# Adafruit_3_5in_480x320_FeatherWing_Rev_B.net
KiCad netlist of a schematic drawn in EAGLE
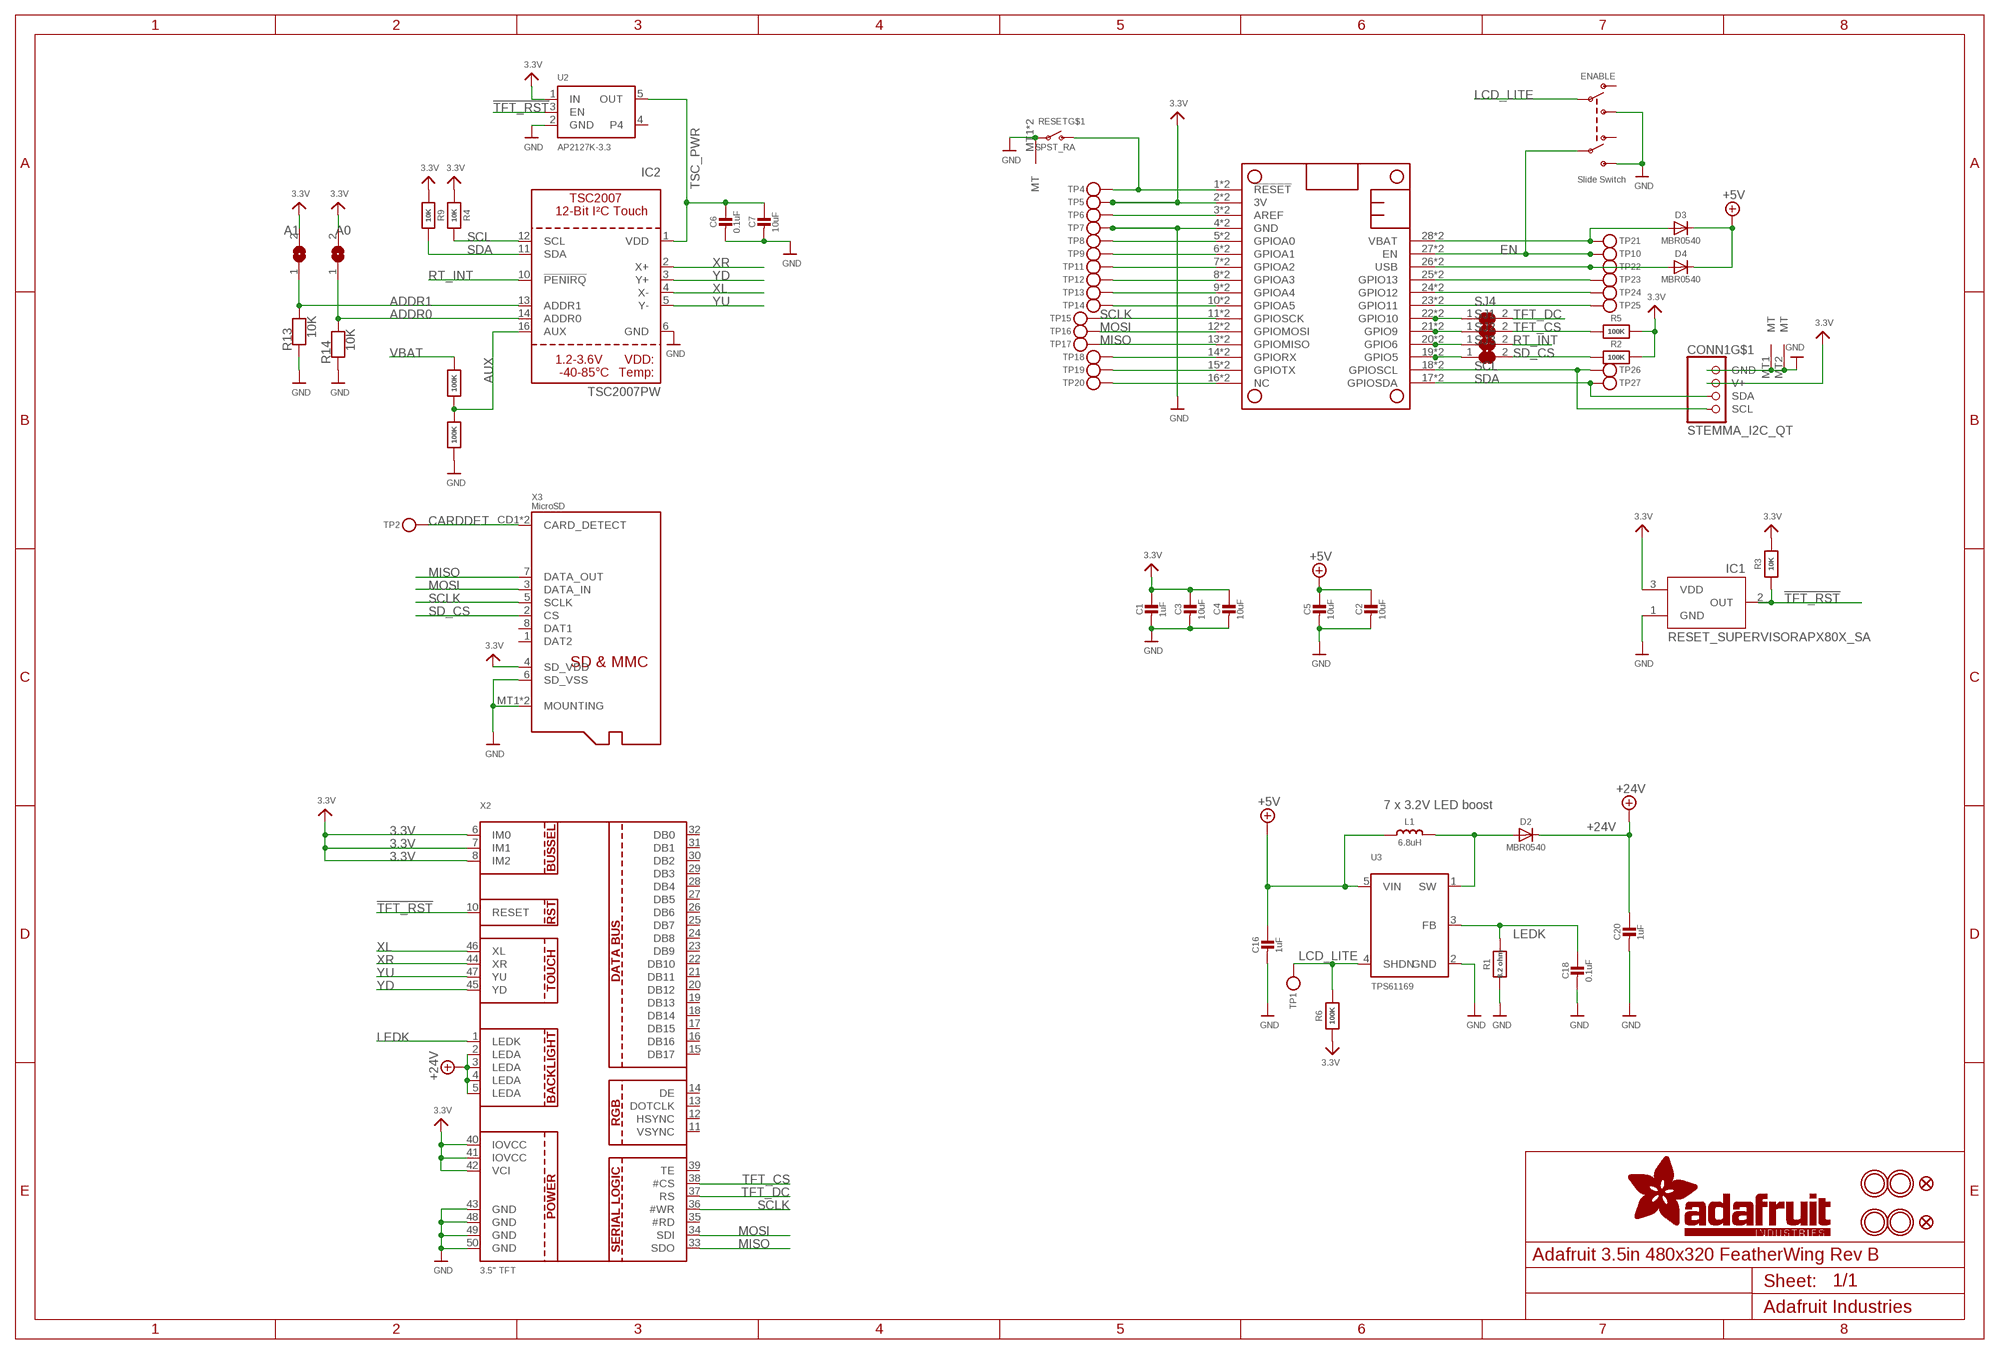
[diagram p0: schematic, sheet 1]

(export (version "E")
  (design (tool "Eeschema 10.0.6"))
  (components
    (comp (ref "C1")
      (value "1uF")
      (footprint "eagle-import:0805-NO")
      (libsource (lib "eagle-import") (part "CAP_CERAMIC0805-NOOUTLINE"))
    )
    (comp (ref "C2")
      (value "10uF")
      (footprint "eagle-import:0805-NO")
      (libsource (lib "eagle-import") (part "CAP_CERAMIC0805-NOOUTLINE"))
    )
    (comp (ref "C3")
      (value "10uF")
      (footprint "eagle-import:0805-NO")
      (libsource (lib "eagle-import") (part "CAP_CERAMIC0805-NOOUTLINE"))
    )
    (comp (ref "C4")
      (value "10uF")
      (footprint "eagle-import:0805-NO")
      (libsource (lib "eagle-import") (part "CAP_CERAMIC0805-NOOUTLINE"))
    )
    (comp (ref "C5")
      (value "10uF")
      (footprint "eagle-import:0805-NO")
      (libsource (lib "eagle-import") (part "CAP_CERAMIC0805-NOOUTLINE"))
    )
    (comp (ref "C6")
      (value "0.1uF")
      (footprint "eagle-import:0603-NO")
      (libsource (lib "eagle-import") (part "CAP_CERAMIC0603_NO"))
    )
    (comp (ref "C7")
      (value "10uF")
      (footprint "eagle-import:0805-NO")
      (libsource (lib "eagle-import") (part "CAP_CERAMIC0805-NOOUTLINE"))
    )
    (comp (ref "C16")
      (value "1uF")
      (footprint "eagle-import:0805-NO")
      (libsource (lib "eagle-import") (part "CAP_CERAMIC0805-NOOUTLINE"))
    )
    (comp (ref "C18")
      (value "0.1uF")
      (footprint "eagle-import:0603-NO")
      (libsource (lib "eagle-import") (part "CAP_CERAMIC0603_NO"))
    )
    (comp (ref "C20")
      (value "1uF")
      (footprint "eagle-import:0805-NO")
      (libsource (lib "eagle-import") (part "CAP_CERAMIC0805-NOOUTLINE"))
    )
    (comp (ref "CONN1")
      (value "STEMMA_I2C_QT")
      (footprint "eagle-import:JST_SH4")
      (libsource (lib "eagle-import") (part "STEMMA_I2C_QT"))
    )
    (comp (ref "D2")
      (value "MBR0540")
      (footprint "eagle-import:SOD-123")
      (libsource (lib "eagle-import") (part "DIODESOD-123"))
    )
    (comp (ref "D3")
      (value "MBR0540")
      (footprint "eagle-import:SOD-123")
      (libsource (lib "eagle-import") (part "DIODESOD-123"))
    )
    (comp (ref "D4")
      (value "MBR0540")
      (footprint "eagle-import:SOD-123")
      (libsource (lib "eagle-import") (part "DIODESOD-123"))
    )
    (comp (ref "ENABLE")
      (value "Slide Switch")
      (footprint "eagle-import:EG1390")
      (libsource (lib "eagle-import") (part "SWITCH_DPDTEG1390"))
    )
    (comp (ref "IC1")
      (value "RESET_SUPERVISORAPX80X_SA")
      (footprint "eagle-import:SOT23-WIDE")
      (libsource (lib "eagle-import") (part "RESET_SUPERVISORAPX80X_SA"))
    )
    (comp (ref "IC2")
      (value "TSC2007PW")
      (footprint "eagle-import:TSSOP16")
      (libsource (lib "eagle-import") (part "TSC2007PW"))
    )
    (comp (ref "ICSP_CLK1")
      (value "A1")
      (footprint "eagle-import:SOLDERJUMPER_ARROW_NOPASTE")
      (libsource (lib "eagle-import") (part "SOLDERJUMPER"))
    )
    (comp (ref "ICSP_CLK2")
      (value "A0")
      (footprint "eagle-import:SOLDERJUMPER_ARROW_NOPASTE")
      (libsource (lib "eagle-import") (part "SOLDERJUMPER"))
    )
    (comp (ref "L1")
      (value "6.8uH")
      (footprint "eagle-import:INDUCTOR_5X5MM_NR5040_NOTHERMALS")
      (libsource (lib "eagle-import") (part "INDUCTORNR5040"))
    )
    (comp (ref "MS2")
      (value "FEATHERWING_SMTDUAL")
      (footprint "eagle-import:FEATHERWING_SMT2")
      (libsource (lib "eagle-import") (part "FEATHERWING_SMTDUAL"))
    )
    (comp (ref "R1")
      (value "8.2 ohm")
      (footprint "eagle-import:0603-NO")
      (libsource (lib "eagle-import") (part "RESISTOR_0603_NOOUT"))
    )
    (comp (ref "R2")
      (value "100K")
      (footprint "eagle-import:0603-NO")
      (libsource (lib "eagle-import") (part "RESISTOR_0603_NOOUT"))
    )
    (comp (ref "R3")
      (value "10K")
      (footprint "eagle-import:0603-NO")
      (libsource (lib "eagle-import") (part "RESISTOR_0603_NOOUT"))
    )
    (comp (ref "R4")
      (value "10K")
      (footprint "eagle-import:0603-NO")
      (libsource (lib "eagle-import") (part "RESISTOR_0603_NOOUT"))
    )
    (comp (ref "R5")
      (value "100K")
      (footprint "eagle-import:0603-NO")
      (libsource (lib "eagle-import") (part "RESISTOR_0603_NOOUT"))
    )
    (comp (ref "R6")
      (value "100K")
      (footprint "eagle-import:0603-NO")
      (libsource (lib "eagle-import") (part "RESISTOR_0603_NOOUT"))
    )
    (comp (ref "R9")
      (value "10K")
      (footprint "eagle-import:0603-NO")
      (libsource (lib "eagle-import") (part "RESISTOR_0603_NOOUT"))
    )
    (comp (ref "R10")
      (value "100K")
      (footprint "eagle-import:0603-NO")
      (libsource (lib "eagle-import") (part "RESISTOR_0603_NOOUT"))
    )
    (comp (ref "R11")
      (value "100K")
      (footprint "eagle-import:0603-NO")
      (libsource (lib "eagle-import") (part "RESISTOR_0603_NOOUT"))
    )
    (comp (ref "R13")
      (value "10K")
      (footprint "eagle-import:0603-NO")
      (libsource (lib "eagle-import") (part "RESISTOR_0603_NOOUT"))
    )
    (comp (ref "R14")
      (value "10K")
      (footprint "eagle-import:0603-NO")
      (libsource (lib "eagle-import") (part "RESISTOR_0603_NOOUT"))
    )
    (comp (ref "RESET")
      (value "SPST_RA")
      (footprint "eagle-import:SPST_TACTILE_RA")
      (libsource (lib "eagle-import") (part "SWITCH_SPST_MNT_TACT_RA"))
    )
    (comp (ref "SJ1")
      (value "SOLDERJUMPER_CLOSED")
      (footprint "eagle-import:SOLDERJUMPER_CLOSEDWIRE")
      (libsource (lib "eagle-import") (part "SOLDERJUMPER_CLOSED"))
    )
    (comp (ref "SJ2")
      (value "SOLDERJUMPER_CLOSED")
      (footprint "eagle-import:SOLDERJUMPER_CLOSEDWIRE")
      (libsource (lib "eagle-import") (part "SOLDERJUMPER_CLOSED"))
    )
    (comp (ref "SJ3")
      (value "SOLDERJUMPER_CLOSED")
      (footprint "eagle-import:SOLDERJUMPER_CLOSEDWIRE")
      (libsource (lib "eagle-import") (part "SOLDERJUMPER_CLOSED"))
    )
    (comp (ref "SJ4")
      (value "SOLDERJUMPER_CLOSED")
      (footprint "eagle-import:SOLDERJUMPER_CLOSEDWIRE")
      (libsource (lib "eagle-import") (part "SOLDERJUMPER_CLOSED"))
    )
    (comp (ref "TP1")
      (value "TESTPOINTPAD2MM")
      (footprint "eagle-import:TESTPOINT_PAD_2MM")
      (libsource (lib "eagle-import") (part "TESTPOINTPAD2MM"))
    )
    (comp (ref "TP2")
      (value "TESTPOINTPAD2MM")
      (footprint "eagle-import:TESTPOINT_PAD_2MM")
      (libsource (lib "eagle-import") (part "TESTPOINTPAD2MM"))
    )
    (comp (ref "TP4")
      (value "TESTPOINTPAD2MM")
      (footprint "eagle-import:TESTPOINT_PAD_2MM")
      (libsource (lib "eagle-import") (part "TESTPOINTPAD2MM"))
    )
    (comp (ref "TP5")
      (value "TESTPOINTPAD2MM")
      (footprint "eagle-import:TESTPOINT_PAD_2MM")
      (libsource (lib "eagle-import") (part "TESTPOINTPAD2MM"))
    )
    (comp (ref "TP6")
      (value "TESTPOINTPAD2MM")
      (footprint "eagle-import:TESTPOINT_PAD_2MM")
      (libsource (lib "eagle-import") (part "TESTPOINTPAD2MM"))
    )
    (comp (ref "TP7")
      (value "TESTPOINTPAD2MM")
      (footprint "eagle-import:TESTPOINT_PAD_2MM")
      (libsource (lib "eagle-import") (part "TESTPOINTPAD2MM"))
    )
    (comp (ref "TP8")
      (value "TESTPOINTPAD2MM")
      (footprint "eagle-import:TESTPOINT_PAD_2MM")
      (libsource (lib "eagle-import") (part "TESTPOINTPAD2MM"))
    )
    (comp (ref "TP9")
      (value "TESTPOINTPAD2MM")
      (footprint "eagle-import:TESTPOINT_PAD_2MM")
      (libsource (lib "eagle-import") (part "TESTPOINTPAD2MM"))
    )
    (comp (ref "TP10")
      (value "TESTPOINTPAD2MM")
      (footprint "eagle-import:TESTPOINT_PAD_2MM")
      (libsource (lib "eagle-import") (part "TESTPOINTPAD2MM"))
    )
    (comp (ref "TP11")
      (value "TESTPOINTPAD2MM")
      (footprint "eagle-import:TESTPOINT_PAD_2MM")
      (libsource (lib "eagle-import") (part "TESTPOINTPAD2MM"))
    )
    (comp (ref "TP12")
      (value "TESTPOINTPAD2MM")
      (footprint "eagle-import:TESTPOINT_PAD_2MM")
      (libsource (lib "eagle-import") (part "TESTPOINTPAD2MM"))
    )
    (comp (ref "TP13")
      (value "TESTPOINTPAD2MM")
      (footprint "eagle-import:TESTPOINT_PAD_2MM")
      (libsource (lib "eagle-import") (part "TESTPOINTPAD2MM"))
    )
    (comp (ref "TP14")
      (value "TESTPOINTPAD2MM")
      (footprint "eagle-import:TESTPOINT_PAD_2MM")
      (libsource (lib "eagle-import") (part "TESTPOINTPAD2MM"))
    )
    (comp (ref "TP15")
      (value "TESTPOINTPAD2MM")
      (footprint "eagle-import:TESTPOINT_PAD_2MM")
      (libsource (lib "eagle-import") (part "TESTPOINTPAD2MM"))
    )
    (comp (ref "TP16")
      (value "TESTPOINTPAD2MM")
      (footprint "eagle-import:TESTPOINT_PAD_2MM")
      (libsource (lib "eagle-import") (part "TESTPOINTPAD2MM"))
    )
    (comp (ref "TP17")
      (value "TESTPOINTPAD2MM")
      (footprint "eagle-import:TESTPOINT_PAD_2MM")
      (libsource (lib "eagle-import") (part "TESTPOINTPAD2MM"))
    )
    (comp (ref "TP18")
      (value "TESTPOINTPAD2MM")
      (footprint "eagle-import:TESTPOINT_PAD_2MM")
      (libsource (lib "eagle-import") (part "TESTPOINTPAD2MM"))
    )
    (comp (ref "TP19")
      (value "TESTPOINTPAD2MM")
      (footprint "eagle-import:TESTPOINT_PAD_2MM")
      (libsource (lib "eagle-import") (part "TESTPOINTPAD2MM"))
    )
    (comp (ref "TP20")
      (value "TESTPOINTPAD2MM")
      (footprint "eagle-import:TESTPOINT_PAD_2MM")
      (libsource (lib "eagle-import") (part "TESTPOINTPAD2MM"))
    )
    (comp (ref "TP21")
      (value "TESTPOINTPAD2MM")
      (footprint "eagle-import:TESTPOINT_PAD_2MM")
      (libsource (lib "eagle-import") (part "TESTPOINTPAD2MM"))
    )
    (comp (ref "TP22")
      (value "TESTPOINTPAD2MM")
      (footprint "eagle-import:TESTPOINT_PAD_2MM")
      (libsource (lib "eagle-import") (part "TESTPOINTPAD2MM"))
    )
    (comp (ref "TP23")
      (value "TESTPOINTPAD2MM")
      (footprint "eagle-import:TESTPOINT_PAD_2MM")
      (libsource (lib "eagle-import") (part "TESTPOINTPAD2MM"))
    )
    (comp (ref "TP24")
      (value "TESTPOINTPAD2MM")
      (footprint "eagle-import:TESTPOINT_PAD_2MM")
      (libsource (lib "eagle-import") (part "TESTPOINTPAD2MM"))
    )
    (comp (ref "TP25")
      (value "TESTPOINTPAD2MM")
      (footprint "eagle-import:TESTPOINT_PAD_2MM")
      (libsource (lib "eagle-import") (part "TESTPOINTPAD2MM"))
    )
    (comp (ref "TP26")
      (value "TESTPOINTPAD2MM")
      (footprint "eagle-import:TESTPOINT_PAD_2MM")
      (libsource (lib "eagle-import") (part "TESTPOINTPAD2MM"))
    )
    (comp (ref "TP27")
      (value "TESTPOINTPAD2MM")
      (footprint "eagle-import:TESTPOINT_PAD_2MM")
      (libsource (lib "eagle-import") (part "TESTPOINTPAD2MM"))
    )
    (comp (ref "U$7")
      (value "MOUNTINGHOLE3.0THIN")
      (footprint "eagle-import:MOUNTINGHOLE_3.0_PLATEDTHIN")
      (libsource (lib "eagle-import") (part "MOUNTINGHOLE3.0THIN"))
    )
    (comp (ref "U$9")
      (value "FIDUCIAL_1MM")
      (footprint "eagle-import:FIDUCIAL_1MM")
      (libsource (lib "eagle-import") (part "FIDUCIAL_1MM"))
    )
    (comp (ref "U$15")
      (value "MOUNTINGHOLE3.0THIN")
      (footprint "eagle-import:MOUNTINGHOLE_3.0_PLATEDTHIN")
      (libsource (lib "eagle-import") (part "MOUNTINGHOLE3.0THIN"))
    )
    (comp (ref "U$16")
      (value "MOUNTINGHOLE3.0THIN")
      (footprint "eagle-import:MOUNTINGHOLE_3.0_PLATEDTHIN")
      (libsource (lib "eagle-import") (part "MOUNTINGHOLE3.0THIN"))
    )
    (comp (ref "U$17")
      (value "MOUNTINGHOLE3.0THIN")
      (footprint "eagle-import:MOUNTINGHOLE_3.0_PLATEDTHIN")
      (libsource (lib "eagle-import") (part "MOUNTINGHOLE3.0THIN"))
    )
    (comp (ref "U$23")
      (value "FIDUCIAL_1MM")
      (footprint "eagle-import:FIDUCIAL_1MM")
      (libsource (lib "eagle-import") (part "FIDUCIAL_1MM"))
    )
    (comp (ref "U2")
      (value "AP2127K-3.3")
      (footprint "eagle-import:SOT23-5")
      (libsource (lib "eagle-import") (part "VREG_SOT23-5"))
    )
    (comp (ref "U3")
      (value "TPS61169")
      (footprint "eagle-import:SC70-5")
      (libsource (lib "eagle-import") (part "VREG_BOOST_5PIN_SC70"))
    )
    (comp (ref "X2")
      (value "3.5\" TFT")
      (footprint "eagle-import:TFT_3.5IN_320X480_50PIN")
      (libsource (lib "eagle-import") (part "DISP_LCD_3.5IN_320X480_50PIN"))
    )
    (comp (ref "X3")
      (value "MicroSD")
      (footprint "eagle-import:MICROSD")
      (libsource (lib "eagle-import") (part "MICROSD"))
    )
  )
  (nets
    (net (code "1") (name "+5V") (class "Default")
      (node (ref "C16") (pin "1") (pinfunction "1_1") (pintype "passive"))
      (node (ref "C2") (pin "1") (pinfunction "1_1") (pintype "passive"))
      (node (ref "C5") (pin "1") (pinfunction "1_1") (pintype "passive"))
      (node (ref "D3") (pin "C") (pinfunction "C_C") (pintype "passive"))
      (node (ref "D4") (pin "C") (pinfunction "C_C") (pintype "passive"))
      (node (ref "L1") (pin "P$1") (pinfunction "1_P$1") (pintype "passive"))
      (node (ref "U3") (pin "5") (pinfunction "VIN_5") (pintype "bidirectional"))
    )
    (net (code "2") (name "+24V") (class "Default")
      (node (ref "C20") (pin "1") (pinfunction "1_1") (pintype "passive"))
      (node (ref "D2") (pin "C") (pinfunction "C_C") (pintype "passive"))
      (node (ref "X2") (pin "2") (pinfunction "LEDA_2") (pintype "bidirectional"))
      (node (ref "X2") (pin "3") (pinfunction "LEDA_3") (pintype "bidirectional"))
      (node (ref "X2") (pin "4") (pinfunction "LEDA_4") (pintype "bidirectional"))
      (node (ref "X2") (pin "5") (pinfunction "LEDA_5") (pintype "bidirectional"))
    )
    (net (code "3") (name "/ADDR0") (class "Default")
      (node (ref "IC2") (pin "14") (pinfunction "ADDR0_14") (pintype "input"))
      (node (ref "ICSP_CLK2") (pin "1") (pinfunction "1_1") (pintype "passive"))
      (node (ref "R14") (pin "2") (pinfunction "2_2") (pintype "passive"))
    )
    (net (code "4") (name "/ADDR1") (class "Default")
      (node (ref "IC2") (pin "13") (pinfunction "ADDR1_13") (pintype "input"))
      (node (ref "ICSP_CLK1") (pin "1") (pinfunction "1_1") (pintype "passive"))
      (node (ref "R13") (pin "2") (pinfunction "2_2") (pintype "passive"))
    )
    (net (code "5") (name "/AUX") (class "Default")
      (node (ref "IC2") (pin "16") (pinfunction "AUX_16") (pintype "input"))
      (node (ref "R10") (pin "1") (pinfunction "1_1") (pintype "passive"))
      (node (ref "R11") (pin "2") (pinfunction "2_2") (pintype "passive"))
    )
    (net (code "6") (name "/CARDDET") (class "Default")
      (node (ref "TP2") (pin "P$1") (pinfunction "P$1_P$1") (pintype "bidirectional"))
      (node (ref "X3") (pin "CD1") (pinfunction "CARD_DETECT_CD1") (pintype "passive"))
      (node (ref "X3") (pin "CD2") (pinfunction "CARD_DETECT_CD2") (pintype "passive"))
    )
    (net (code "7") (name "/EN") (class "Default")
      (node (ref "ENABLE") (pin "P2") (pinfunction "P2_P2") (pintype "passive"))
      (node (ref "MS2") (pin "27") (pinfunction "EN_27") (pintype "passive"))
      (node (ref "MS2") (pin "27'") (pinfunction "EN_27'") (pintype "passive"))
      (node (ref "TP10") (pin "P$1") (pinfunction "P$1_P$1") (pintype "bidirectional"))
    )
    (net (code "8") (name "/LCD_LITE") (class "Default")
      (node (ref "ENABLE") (pin "P1") (pinfunction "P1_P1") (pintype "passive"))
      (node (ref "R6") (pin "2") (pinfunction "2_2") (pintype "passive"))
      (node (ref "TP1") (pin "P$1") (pinfunction "P$1_P$1") (pintype "bidirectional"))
      (node (ref "U3") (pin "4") (pinfunction "SHDN_4") (pintype "bidirectional"))
    )
    (net (code "9") (name "/LEDK") (class "Default")
      (node (ref "C18") (pin "1") (pinfunction "1_1") (pintype "passive"))
      (node (ref "R1") (pin "2") (pinfunction "2_2") (pintype "passive"))
      (node (ref "U3") (pin "3") (pinfunction "FB_3") (pintype "bidirectional"))
      (node (ref "X2") (pin "1") (pinfunction "LEDK_1") (pintype "bidirectional"))
    )
    (net (code "10") (name "/MISO") (class "Default")
      (node (ref "MS2") (pin "13") (pinfunction "GPIOMISO_13") (pintype "bidirectional"))
      (node (ref "MS2") (pin "13'") (pinfunction "GPIOMISO_13'") (pintype "bidirectional"))
      (node (ref "TP17") (pin "P$1") (pinfunction "P$1_P$1") (pintype "bidirectional"))
      (node (ref "X2") (pin "33") (pinfunction "SDO_33") (pintype "bidirectional"))
      (node (ref "X3") (pin "7") (pinfunction "DATA_OUT_7") (pintype "output"))
    )
    (net (code "11") (name "/MOSI") (class "Default")
      (node (ref "MS2") (pin "12") (pinfunction "GPIOMOSI_12") (pintype "bidirectional"))
      (node (ref "MS2") (pin "12'") (pinfunction "GPIOMOSI_12'") (pintype "bidirectional"))
      (node (ref "TP16") (pin "P$1") (pinfunction "P$1_P$1") (pintype "bidirectional"))
      (node (ref "X2") (pin "34") (pinfunction "SDI_34") (pintype "bidirectional"))
      (node (ref "X3") (pin "3") (pinfunction "DATA_IN_3") (pintype "input"))
    )
    (net (code "12") (name "/RT_INT") (class "Default")
      (node (ref "IC2") (pin "10") (pinfunction "~{PENIRQ}_10") (pintype "output"))
      (node (ref "SJ2") (pin "2") (pinfunction "2_2") (pintype "passive"))
    )
    (net (code "13") (name "/SCL") (class "Default")
      (node (ref "CONN1") (pin "4") (pinfunction "SCL_4") (pintype "passive"))
      (node (ref "IC2") (pin "12") (pinfunction "SCL_12") (pintype "bidirectional"))
      (node (ref "MS2") (pin "18") (pinfunction "GPIOSCL_18") (pintype "bidirectional"))
      (node (ref "MS2") (pin "18'") (pinfunction "GPIOSCL_18'") (pintype "bidirectional"))
      (node (ref "R4") (pin "2") (pinfunction "2_2") (pintype "passive"))
      (node (ref "TP26") (pin "P$1") (pinfunction "P$1_P$1") (pintype "bidirectional"))
    )
    (net (code "14") (name "/SCLK") (class "Default")
      (node (ref "MS2") (pin "11") (pinfunction "GPIOSCK_11") (pintype "bidirectional"))
      (node (ref "MS2") (pin "11'") (pinfunction "GPIOSCK_11'") (pintype "bidirectional"))
      (node (ref "TP15") (pin "P$1") (pinfunction "P$1_P$1") (pintype "bidirectional"))
      (node (ref "X2") (pin "36") (pinfunction "#WR_36") (pintype "bidirectional"))
      (node (ref "X3") (pin "5") (pinfunction "SCLK_5") (pintype "input"))
    )
    (net (code "15") (name "/SDA") (class "Default")
      (node (ref "CONN1") (pin "3") (pinfunction "SDA_3") (pintype "passive"))
      (node (ref "IC2") (pin "11") (pinfunction "SDA_11") (pintype "bidirectional"))
      (node (ref "MS2") (pin "17") (pinfunction "GPIOSDA_17") (pintype "bidirectional"))
      (node (ref "MS2") (pin "17'") (pinfunction "GPIOSDA_17'") (pintype "bidirectional"))
      (node (ref "R9") (pin "2") (pinfunction "2_2") (pintype "passive"))
      (node (ref "TP27") (pin "P$1") (pinfunction "P$1_P$1") (pintype "bidirectional"))
    )
    (net (code "16") (name "/SD_CS") (class "Default")
      (node (ref "R2") (pin "1") (pinfunction "1_1") (pintype "passive"))
      (node (ref "SJ3") (pin "2") (pinfunction "2_2") (pintype "passive"))
      (node (ref "X3") (pin "2") (pinfunction "CS_2") (pintype "input"))
    )
    (net (code "17") (name "/TFT_CS") (class "Default")
      (node (ref "R5") (pin "1") (pinfunction "1_1") (pintype "passive"))
      (node (ref "SJ1") (pin "2") (pinfunction "2_2") (pintype "passive"))
      (node (ref "X2") (pin "38") (pinfunction "#CS_38") (pintype "bidirectional"))
    )
    (net (code "18") (name "/TFT_DC") (class "Default")
      (node (ref "SJ4") (pin "2") (pinfunction "2_2") (pintype "passive"))
      (node (ref "X2") (pin "37") (pinfunction "RS_37") (pintype "bidirectional"))
    )
    (net (code "19") (name "/TSC_PWR") (class "Default")
      (node (ref "C6") (pin "1") (pinfunction "1_1") (pintype "passive"))
      (node (ref "C7") (pin "1") (pinfunction "1_1") (pintype "passive"))
      (node (ref "IC2") (pin "1") (pinfunction "VDD_1") (pintype "bidirectional"))
      (node (ref "U2") (pin "5") (pinfunction "OUT_5") (pintype "power_in"))
    )
    (net (code "20") (name "/VBAT") (class "Default")
      (node (ref "D3") (pin "A") (pinfunction "A_A") (pintype "passive"))
      (node (ref "MS2") (pin "28") (pinfunction "VBAT_28") (pintype "power_in"))
      (node (ref "MS2") (pin "28'") (pinfunction "VBAT_28'") (pintype "power_in"))
      (node (ref "R10") (pin "2") (pinfunction "2_2") (pintype "passive"))
      (node (ref "TP21") (pin "P$1") (pinfunction "P$1_P$1") (pintype "bidirectional"))
    )
    (net (code "21") (name "/XL") (class "Default")
      (node (ref "IC2") (pin "4") (pinfunction "X-_4") (pintype "input"))
      (node (ref "X2") (pin "46") (pinfunction "XL_46") (pintype "bidirectional"))
    )
    (net (code "22") (name "/XR") (class "Default")
      (node (ref "IC2") (pin "2") (pinfunction "X+_2") (pintype "input"))
      (node (ref "X2") (pin "44") (pinfunction "XR_44") (pintype "bidirectional"))
    )
    (net (code "23") (name "/YD") (class "Default")
      (node (ref "IC2") (pin "3") (pinfunction "Y+_3") (pintype "input"))
      (node (ref "X2") (pin "45") (pinfunction "YD_45") (pintype "bidirectional"))
    )
    (net (code "24") (name "/YU") (class "Default")
      (node (ref "IC2") (pin "5") (pinfunction "Y-_5") (pintype "input"))
      (node (ref "X2") (pin "47") (pinfunction "YU_47") (pintype "bidirectional"))
    )
    (net (code "25") (name "/~{TFT_RST}") (class "Default")
      (node (ref "IC1") (pin "2") (pinfunction "OUT_2") (pintype "output"))
      (node (ref "R3") (pin "1") (pinfunction "1_1") (pintype "passive"))
      (node (ref "U2") (pin "3") (pinfunction "EN_3") (pintype "input"))
      (node (ref "X2") (pin "10") (pinfunction "RESET_10") (pintype "bidirectional"))
    )
    (net (code "26") (name "3.3V") (class "Default")
      (node (ref "C1") (pin "1") (pinfunction "1_1") (pintype "passive"))
      (node (ref "C3") (pin "1") (pinfunction "1_1") (pintype "passive"))
      (node (ref "C4") (pin "1") (pinfunction "1_1") (pintype "passive"))
      (node (ref "CONN1") (pin "2") (pinfunction "V+_2") (pintype "passive"))
      (node (ref "IC1") (pin "3") (pinfunction "VDD_3") (pintype "power_in"))
      (node (ref "ICSP_CLK1") (pin "2") (pinfunction "2_2") (pintype "passive"))
      (node (ref "ICSP_CLK2") (pin "2") (pinfunction "2_2") (pintype "passive"))
      (node (ref "MS2") (pin "2") (pinfunction "3V_2") (pintype "power_in"))
      (node (ref "MS2") (pin "2'") (pinfunction "3V_2'") (pintype "power_in"))
      (node (ref "R2") (pin "2") (pinfunction "2_2") (pintype "passive"))
      (node (ref "R3") (pin "2") (pinfunction "2_2") (pintype "passive"))
      (node (ref "R4") (pin "1") (pinfunction "1_1") (pintype "passive"))
      (node (ref "R5") (pin "2") (pinfunction "2_2") (pintype "passive"))
      (node (ref "R6") (pin "1") (pinfunction "1_1") (pintype "passive"))
      (node (ref "R9") (pin "1") (pinfunction "1_1") (pintype "passive"))
      (node (ref "TP5") (pin "P$1") (pinfunction "P$1_P$1") (pintype "bidirectional"))
      (node (ref "U2") (pin "1") (pinfunction "IN_1") (pintype "power_in"))
      (node (ref "X2") (pin "40") (pinfunction "IOVCC_40") (pintype "bidirectional"))
      (node (ref "X2") (pin "41") (pinfunction "IOVCC_41") (pintype "bidirectional"))
      (node (ref "X2") (pin "42") (pinfunction "VCI_42") (pintype "bidirectional"))
      (node (ref "X2") (pin "6") (pinfunction "IM0_6") (pintype "bidirectional"))
      (node (ref "X2") (pin "7") (pinfunction "IM1_7") (pintype "bidirectional"))
      (node (ref "X2") (pin "8") (pinfunction "IM2_8") (pintype "bidirectional"))
      (node (ref "X3") (pin "4") (pinfunction "SD_VDD_4") (pintype "power_in"))
    )
    (net (code "27") (name "GND") (class "Default")
      (node (ref "C1") (pin "2") (pinfunction "2_2") (pintype "passive"))
      (node (ref "C16") (pin "2") (pinfunction "2_2") (pintype "passive"))
      (node (ref "C18") (pin "2") (pinfunction "2_2") (pintype "passive"))
      (node (ref "C2") (pin "2") (pinfunction "2_2") (pintype "passive"))
      (node (ref "C20") (pin "2") (pinfunction "2_2") (pintype "passive"))
      (node (ref "C3") (pin "2") (pinfunction "2_2") (pintype "passive"))
      (node (ref "C4") (pin "2") (pinfunction "2_2") (pintype "passive"))
      (node (ref "C5") (pin "2") (pinfunction "2_2") (pintype "passive"))
      (node (ref "C6") (pin "2") (pinfunction "2_2") (pintype "passive"))
      (node (ref "C7") (pin "2") (pinfunction "2_2") (pintype "passive"))
      (node (ref "CONN1") (pin "1") (pinfunction "GND_1") (pintype "passive"))
      (node (ref "CONN1") (pin "MT1") (pinfunction "MT_MT1") (pintype "bidirectional"))
      (node (ref "CONN1") (pin "MT2") (pinfunction "MT_MT2") (pintype "bidirectional"))
      (node (ref "ENABLE") (pin "S1") (pinfunction "S1_S1") (pintype "passive"))
      (node (ref "ENABLE") (pin "S2") (pinfunction "S2_S2") (pintype "passive"))
      (node (ref "IC1") (pin "1") (pinfunction "GND_1") (pintype "power_in"))
      (node (ref "IC2") (pin "6") (pinfunction "GND_6") (pintype "bidirectional"))
      (node (ref "MS2") (pin "4") (pinfunction "GND_4") (pintype "power_in"))
      (node (ref "MS2") (pin "4'") (pinfunction "GND_4'") (pintype "power_in"))
      (node (ref "R1") (pin "1") (pinfunction "1_1") (pintype "passive"))
      (node (ref "R11") (pin "1") (pinfunction "1_1") (pintype "passive"))
      (node (ref "R13") (pin "1") (pinfunction "1_1") (pintype "passive"))
      (node (ref "R14") (pin "1") (pinfunction "1_1") (pintype "passive"))
      (node (ref "RESET") (pin "1") (pinfunction "P_1") (pintype "passive"))
      (node (ref "RESET") (pin "MT1") (pinfunction "MT_MT1") (pintype "bidirectional"))
      (node (ref "RESET") (pin "MT2") (pinfunction "MT_MT2") (pintype "bidirectional"))
      (node (ref "TP7") (pin "P$1") (pinfunction "P$1_P$1") (pintype "bidirectional"))
      (node (ref "U2") (pin "2") (pinfunction "GND_2") (pintype "power_in"))
      (node (ref "U3") (pin "2") (pinfunction "GND_2") (pintype "bidirectional"))
      (node (ref "X2") (pin "43") (pinfunction "GND_43") (pintype "bidirectional"))
      (node (ref "X2") (pin "48") (pinfunction "GND_48") (pintype "bidirectional"))
      (node (ref "X2") (pin "49") (pinfunction "GND_49") (pintype "bidirectional"))
      (node (ref "X2") (pin "50") (pinfunction "GND_50") (pintype "bidirectional"))
      (node (ref "X3") (pin "6") (pinfunction "SD_VSS_6") (pintype "power_in"))
      (node (ref "X3") (pin "MT1") (pinfunction "MOUNTING_MT1") (pintype "passive"))
      (node (ref "X3") (pin "MT2") (pinfunction "MOUNTING_MT2") (pintype "passive"))
    )
    (net (code "28") (name "Net-(D4-PadA)") (class "Default")
      (node (ref "D4") (pin "A") (pinfunction "A_A") (pintype "passive"))
      (node (ref "MS2") (pin "26") (pinfunction "USB_26") (pintype "power_in"))
      (node (ref "MS2") (pin "26'") (pinfunction "USB_26'") (pintype "power_in"))
      (node (ref "TP22") (pin "P$1") (pinfunction "P$1_P$1") (pintype "bidirectional"))
    )
    (net (code "29") (name "Net-(L1-2)") (class "Default")
      (node (ref "D2") (pin "A") (pinfunction "A_A") (pintype "passive"))
      (node (ref "L1") (pin "P$2") (pinfunction "2_P$2") (pintype "passive"))
      (node (ref "U3") (pin "1") (pinfunction "SW_1") (pintype "bidirectional"))
    )
    (net (code "30") (name "Net-(MS2-AREF-Pad3')") (class "Default")
      (node (ref "MS2") (pin "3") (pinfunction "AREF_3") (pintype "passive"))
      (node (ref "MS2") (pin "3'") (pinfunction "AREF_3'") (pintype "passive"))
      (node (ref "TP6") (pin "P$1") (pinfunction "P$1_P$1") (pintype "bidirectional"))
    )
    (net (code "31") (name "Net-(MS2-GPIO5-Pad19')") (class "Default")
      (node (ref "MS2") (pin "19") (pinfunction "GPIO5_19") (pintype "bidirectional"))
      (node (ref "MS2") (pin "19'") (pinfunction "GPIO5_19'") (pintype "bidirectional"))
      (node (ref "SJ3") (pin "1") (pinfunction "1_1") (pintype "passive"))
    )
    (net (code "32") (name "Net-(MS2-GPIO6-Pad20')") (class "Default")
      (node (ref "MS2") (pin "20") (pinfunction "GPIO6_20") (pintype "bidirectional"))
      (node (ref "MS2") (pin "20'") (pinfunction "GPIO6_20'") (pintype "bidirectional"))
      (node (ref "SJ2") (pin "1") (pinfunction "1_1") (pintype "passive"))
    )
    (net (code "33") (name "Net-(MS2-GPIO9-Pad21')") (class "Default")
      (node (ref "MS2") (pin "21") (pinfunction "GPIO9_21") (pintype "bidirectional"))
      (node (ref "MS2") (pin "21'") (pinfunction "GPIO9_21'") (pintype "bidirectional"))
      (node (ref "SJ1") (pin "1") (pinfunction "1_1") (pintype "passive"))
    )
    (net (code "34") (name "Net-(MS2-GPIO10-Pad22')") (class "Default")
      (node (ref "MS2") (pin "22") (pinfunction "GPIO10_22") (pintype "bidirectional"))
      (node (ref "MS2") (pin "22'") (pinfunction "GPIO10_22'") (pintype "bidirectional"))
      (node (ref "SJ4") (pin "1") (pinfunction "1_1") (pintype "passive"))
    )
    (net (code "35") (name "Net-(MS2-GPIO11-Pad23')") (class "Default")
      (node (ref "MS2") (pin "23") (pinfunction "GPIO11_23") (pintype "bidirectional"))
      (node (ref "MS2") (pin "23'") (pinfunction "GPIO11_23'") (pintype "bidirectional"))
      (node (ref "TP25") (pin "P$1") (pinfunction "P$1_P$1") (pintype "bidirectional"))
    )
    (net (code "36") (name "Net-(MS2-GPIO12-Pad24')") (class "Default")
      (node (ref "MS2") (pin "24") (pinfunction "GPIO12_24") (pintype "bidirectional"))
      (node (ref "MS2") (pin "24'") (pinfunction "GPIO12_24'") (pintype "bidirectional"))
      (node (ref "TP24") (pin "P$1") (pinfunction "P$1_P$1") (pintype "bidirectional"))
    )
    (net (code "37") (name "Net-(MS2-GPIO13-Pad25')") (class "Default")
      (node (ref "MS2") (pin "25") (pinfunction "GPIO13_25") (pintype "bidirectional"))
      (node (ref "MS2") (pin "25'") (pinfunction "GPIO13_25'") (pintype "bidirectional"))
      (node (ref "TP23") (pin "P$1") (pinfunction "P$1_P$1") (pintype "bidirectional"))
    )
    (net (code "38") (name "Net-(MS2-GPIOA0-Pad5')") (class "Default")
      (node (ref "MS2") (pin "5") (pinfunction "GPIOA0_5") (pintype "bidirectional"))
      (node (ref "MS2") (pin "5'") (pinfunction "GPIOA0_5'") (pintype "bidirectional"))
      (node (ref "TP8") (pin "P$1") (pinfunction "P$1_P$1") (pintype "bidirectional"))
    )
    (net (code "39") (name "Net-(MS2-GPIOA1-Pad6')") (class "Default")
      (node (ref "MS2") (pin "6") (pinfunction "GPIOA1_6") (pintype "bidirectional"))
      (node (ref "MS2") (pin "6'") (pinfunction "GPIOA1_6'") (pintype "bidirectional"))
      (node (ref "TP9") (pin "P$1") (pinfunction "P$1_P$1") (pintype "bidirectional"))
    )
    (net (code "40") (name "Net-(MS2-GPIOA2-Pad7')") (class "Default")
      (node (ref "MS2") (pin "7") (pinfunction "GPIOA2_7") (pintype "bidirectional"))
      (node (ref "MS2") (pin "7'") (pinfunction "GPIOA2_7'") (pintype "bidirectional"))
      (node (ref "TP11") (pin "P$1") (pinfunction "P$1_P$1") (pintype "bidirectional"))
    )
    (net (code "41") (name "Net-(MS2-GPIOA3-Pad8')") (class "Default")
      (node (ref "MS2") (pin "8") (pinfunction "GPIOA3_8") (pintype "bidirectional"))
      (node (ref "MS2") (pin "8'") (pinfunction "GPIOA3_8'") (pintype "bidirectional"))
      (node (ref "TP12") (pin "P$1") (pinfunction "P$1_P$1") (pintype "bidirectional"))
    )
    (net (code "42") (name "Net-(MS2-GPIOA4-Pad9')") (class "Default")
      (node (ref "MS2") (pin "9") (pinfunction "GPIOA4_9") (pintype "bidirectional"))
      (node (ref "MS2") (pin "9'") (pinfunction "GPIOA4_9'") (pintype "bidirectional"))
      (node (ref "TP13") (pin "P$1") (pinfunction "P$1_P$1") (pintype "bidirectional"))
    )
    (net (code "43") (name "Net-(MS2-GPIOA5-Pad10')") (class "Default")
      (node (ref "MS2") (pin "10") (pinfunction "GPIOA5_10") (pintype "bidirectional"))
      (node (ref "MS2") (pin "10'") (pinfunction "GPIOA5_10'") (pintype "bidirectional"))
      (node (ref "TP14") (pin "P$1") (pinfunction "P$1_P$1") (pintype "bidirectional"))
    )
    (net (code "44") (name "Net-(MS2-GPIORX-Pad14')") (class "Default")
      (node (ref "MS2") (pin "14") (pinfunction "GPIORX_14") (pintype "bidirectional"))
      (node (ref "MS2") (pin "14'") (pinfunction "GPIORX_14'") (pintype "bidirectional"))
      (node (ref "TP18") (pin "P$1") (pinfunction "P$1_P$1") (pintype "bidirectional"))
    )
    (net (code "45") (name "Net-(MS2-GPIOTX-Pad15')") (class "Default")
      (node (ref "MS2") (pin "15") (pinfunction "GPIOTX_15") (pintype "bidirectional"))
      (node (ref "MS2") (pin "15'") (pinfunction "GPIOTX_15'") (pintype "bidirectional"))
      (node (ref "TP19") (pin "P$1") (pinfunction "P$1_P$1") (pintype "bidirectional"))
    )
    (net (code "46") (name "Net-(MS2-NC-Pad16')") (class "Default")
      (node (ref "MS2") (pin "16") (pinfunction "NC_16") (pintype "passive"))
      (node (ref "MS2") (pin "16'") (pinfunction "NC_16'") (pintype "passive"))
      (node (ref "TP20") (pin "P$1") (pinfunction "P$1_P$1") (pintype "bidirectional"))
    )
    (net (code "47") (name "Net-(RESETA-S)") (class "Default")
      (node (ref "MS2") (pin "1") (pinfunction "~{RESET}_1") (pintype "input"))
      (node (ref "MS2") (pin "1'") (pinfunction "~{RESET}_1'") (pintype "input"))
      (node (ref "RESET") (pin "2") (pinfunction "S_2") (pintype "passive"))
      (node (ref "TP4") (pin "P$1") (pinfunction "P$1_P$1") (pintype "bidirectional"))
    )
    (net (code "48") (name "unconnected-(ENABLE-PadO1)") (class "Default")
      (node (ref "ENABLE") (pin "O1") (pinfunction "O1_O1") (pintype "passive"))
    )
    (net (code "49") (name "unconnected-(ENABLE-PadO2)") (class "Default")
      (node (ref "ENABLE") (pin "O2") (pinfunction "O2_O2") (pintype "passive"))
    )
    (net (code "50") (name "unconnected-(U2-P4-Pad4)") (class "Default")
      (node (ref "U2") (pin "4") (pinfunction "P4_4") (pintype "bidirectional"))
    )
    (net (code "51") (name "unconnected-(X2-#RD-Pad35)") (class "Default")
      (node (ref "X2") (pin "35") (pinfunction "#RD_35") (pintype "bidirectional"))
    )
    (net (code "52") (name "unconnected-(X2-DB0-Pad32)") (class "Default")
      (node (ref "X2") (pin "32") (pinfunction "DB0_32") (pintype "bidirectional"))
    )
    (net (code "53") (name "unconnected-(X2-DB1-Pad31)") (class "Default")
      (node (ref "X2") (pin "31") (pinfunction "DB1_31") (pintype "bidirectional"))
    )
    (net (code "54") (name "unconnected-(X2-DB2-Pad30)") (class "Default")
      (node (ref "X2") (pin "30") (pinfunction "DB2_30") (pintype "bidirectional"))
    )
    (net (code "55") (name "unconnected-(X2-DB3-Pad29)") (class "Default")
      (node (ref "X2") (pin "29") (pinfunction "DB3_29") (pintype "bidirectional"))
    )
    (net (code "56") (name "unconnected-(X2-DB4-Pad28)") (class "Default")
      (node (ref "X2") (pin "28") (pinfunction "DB4_28") (pintype "bidirectional"))
    )
    (net (code "57") (name "unconnected-(X2-DB5-Pad27)") (class "Default")
      (node (ref "X2") (pin "27") (pinfunction "DB5_27") (pintype "bidirectional"))
    )
    (net (code "58") (name "unconnected-(X2-DB6-Pad26)") (class "Default")
      (node (ref "X2") (pin "26") (pinfunction "DB6_26") (pintype "bidirectional"))
    )
    (net (code "59") (name "unconnected-(X2-DB7-Pad25)") (class "Default")
      (node (ref "X2") (pin "25") (pinfunction "DB7_25") (pintype "bidirectional"))
    )
    (net (code "60") (name "unconnected-(X2-DB8-Pad24)") (class "Default")
      (node (ref "X2") (pin "24") (pinfunction "DB8_24") (pintype "bidirectional"))
    )
    (net (code "61") (name "unconnected-(X2-DB9-Pad23)") (class "Default")
      (node (ref "X2") (pin "23") (pinfunction "DB9_23") (pintype "bidirectional"))
    )
    (net (code "62") (name "unconnected-(X2-DB10-Pad22)") (class "Default")
      (node (ref "X2") (pin "22") (pinfunction "DB10_22") (pintype "bidirectional"))
    )
    (net (code "63") (name "unconnected-(X2-DB11-Pad21)") (class "Default")
      (node (ref "X2") (pin "21") (pinfunction "DB11_21") (pintype "bidirectional"))
    )
    (net (code "64") (name "unconnected-(X2-DB12-Pad20)") (class "Default")
      (node (ref "X2") (pin "20") (pinfunction "DB12_20") (pintype "bidirectional"))
    )
    (net (code "65") (name "unconnected-(X2-DB13-Pad19)") (class "Default")
      (node (ref "X2") (pin "19") (pinfunction "DB13_19") (pintype "bidirectional"))
    )
    (net (code "66") (name "unconnected-(X2-DB14-Pad18)") (class "Default")
      (node (ref "X2") (pin "18") (pinfunction "DB14_18") (pintype "bidirectional"))
    )
    (net (code "67") (name "unconnected-(X2-DB15-Pad17)") (class "Default")
      (node (ref "X2") (pin "17") (pinfunction "DB15_17") (pintype "bidirectional"))
    )
    (net (code "68") (name "unconnected-(X2-DB16-Pad16)") (class "Default")
      (node (ref "X2") (pin "16") (pinfunction "DB16_16") (pintype "bidirectional"))
    )
    (net (code "69") (name "unconnected-(X2-DB17-Pad15)") (class "Default")
      (node (ref "X2") (pin "15") (pinfunction "DB17_15") (pintype "bidirectional"))
    )
    (net (code "70") (name "unconnected-(X2-DE-Pad14)") (class "Default")
      (node (ref "X2") (pin "14") (pinfunction "DE_14") (pintype "bidirectional"))
    )
    (net (code "71") (name "unconnected-(X2-DOTCLK-Pad13)") (class "Default")
      (node (ref "X2") (pin "13") (pinfunction "DOTCLK_13") (pintype "bidirectional"))
    )
    (net (code "72") (name "unconnected-(X2-HSYNC-Pad12)") (class "Default")
      (node (ref "X2") (pin "12") (pinfunction "HSYNC_12") (pintype "bidirectional"))
    )
    (net (code "73") (name "unconnected-(X2-TE-Pad39)") (class "Default")
      (node (ref "X2") (pin "39") (pinfunction "TE_39") (pintype "bidirectional"))
    )
    (net (code "74") (name "unconnected-(X2-VSYNC-Pad11)") (class "Default")
      (node (ref "X2") (pin "11") (pinfunction "VSYNC_11") (pintype "bidirectional"))
    )
    (net (code "75") (name "unconnected-(X3-DAT1-Pad8)") (class "Default")
      (node (ref "X3") (pin "8") (pinfunction "DAT1_8") (pintype "bidirectional"))
    )
    (net (code "76") (name "unconnected-(X3-DAT2-Pad1)") (class "Default")
      (node (ref "X3") (pin "1") (pinfunction "DAT2_1") (pintype "bidirectional"))
    )
  )
)
